# main.net
KiCad netlist of a schematic drawn in Altium Designer
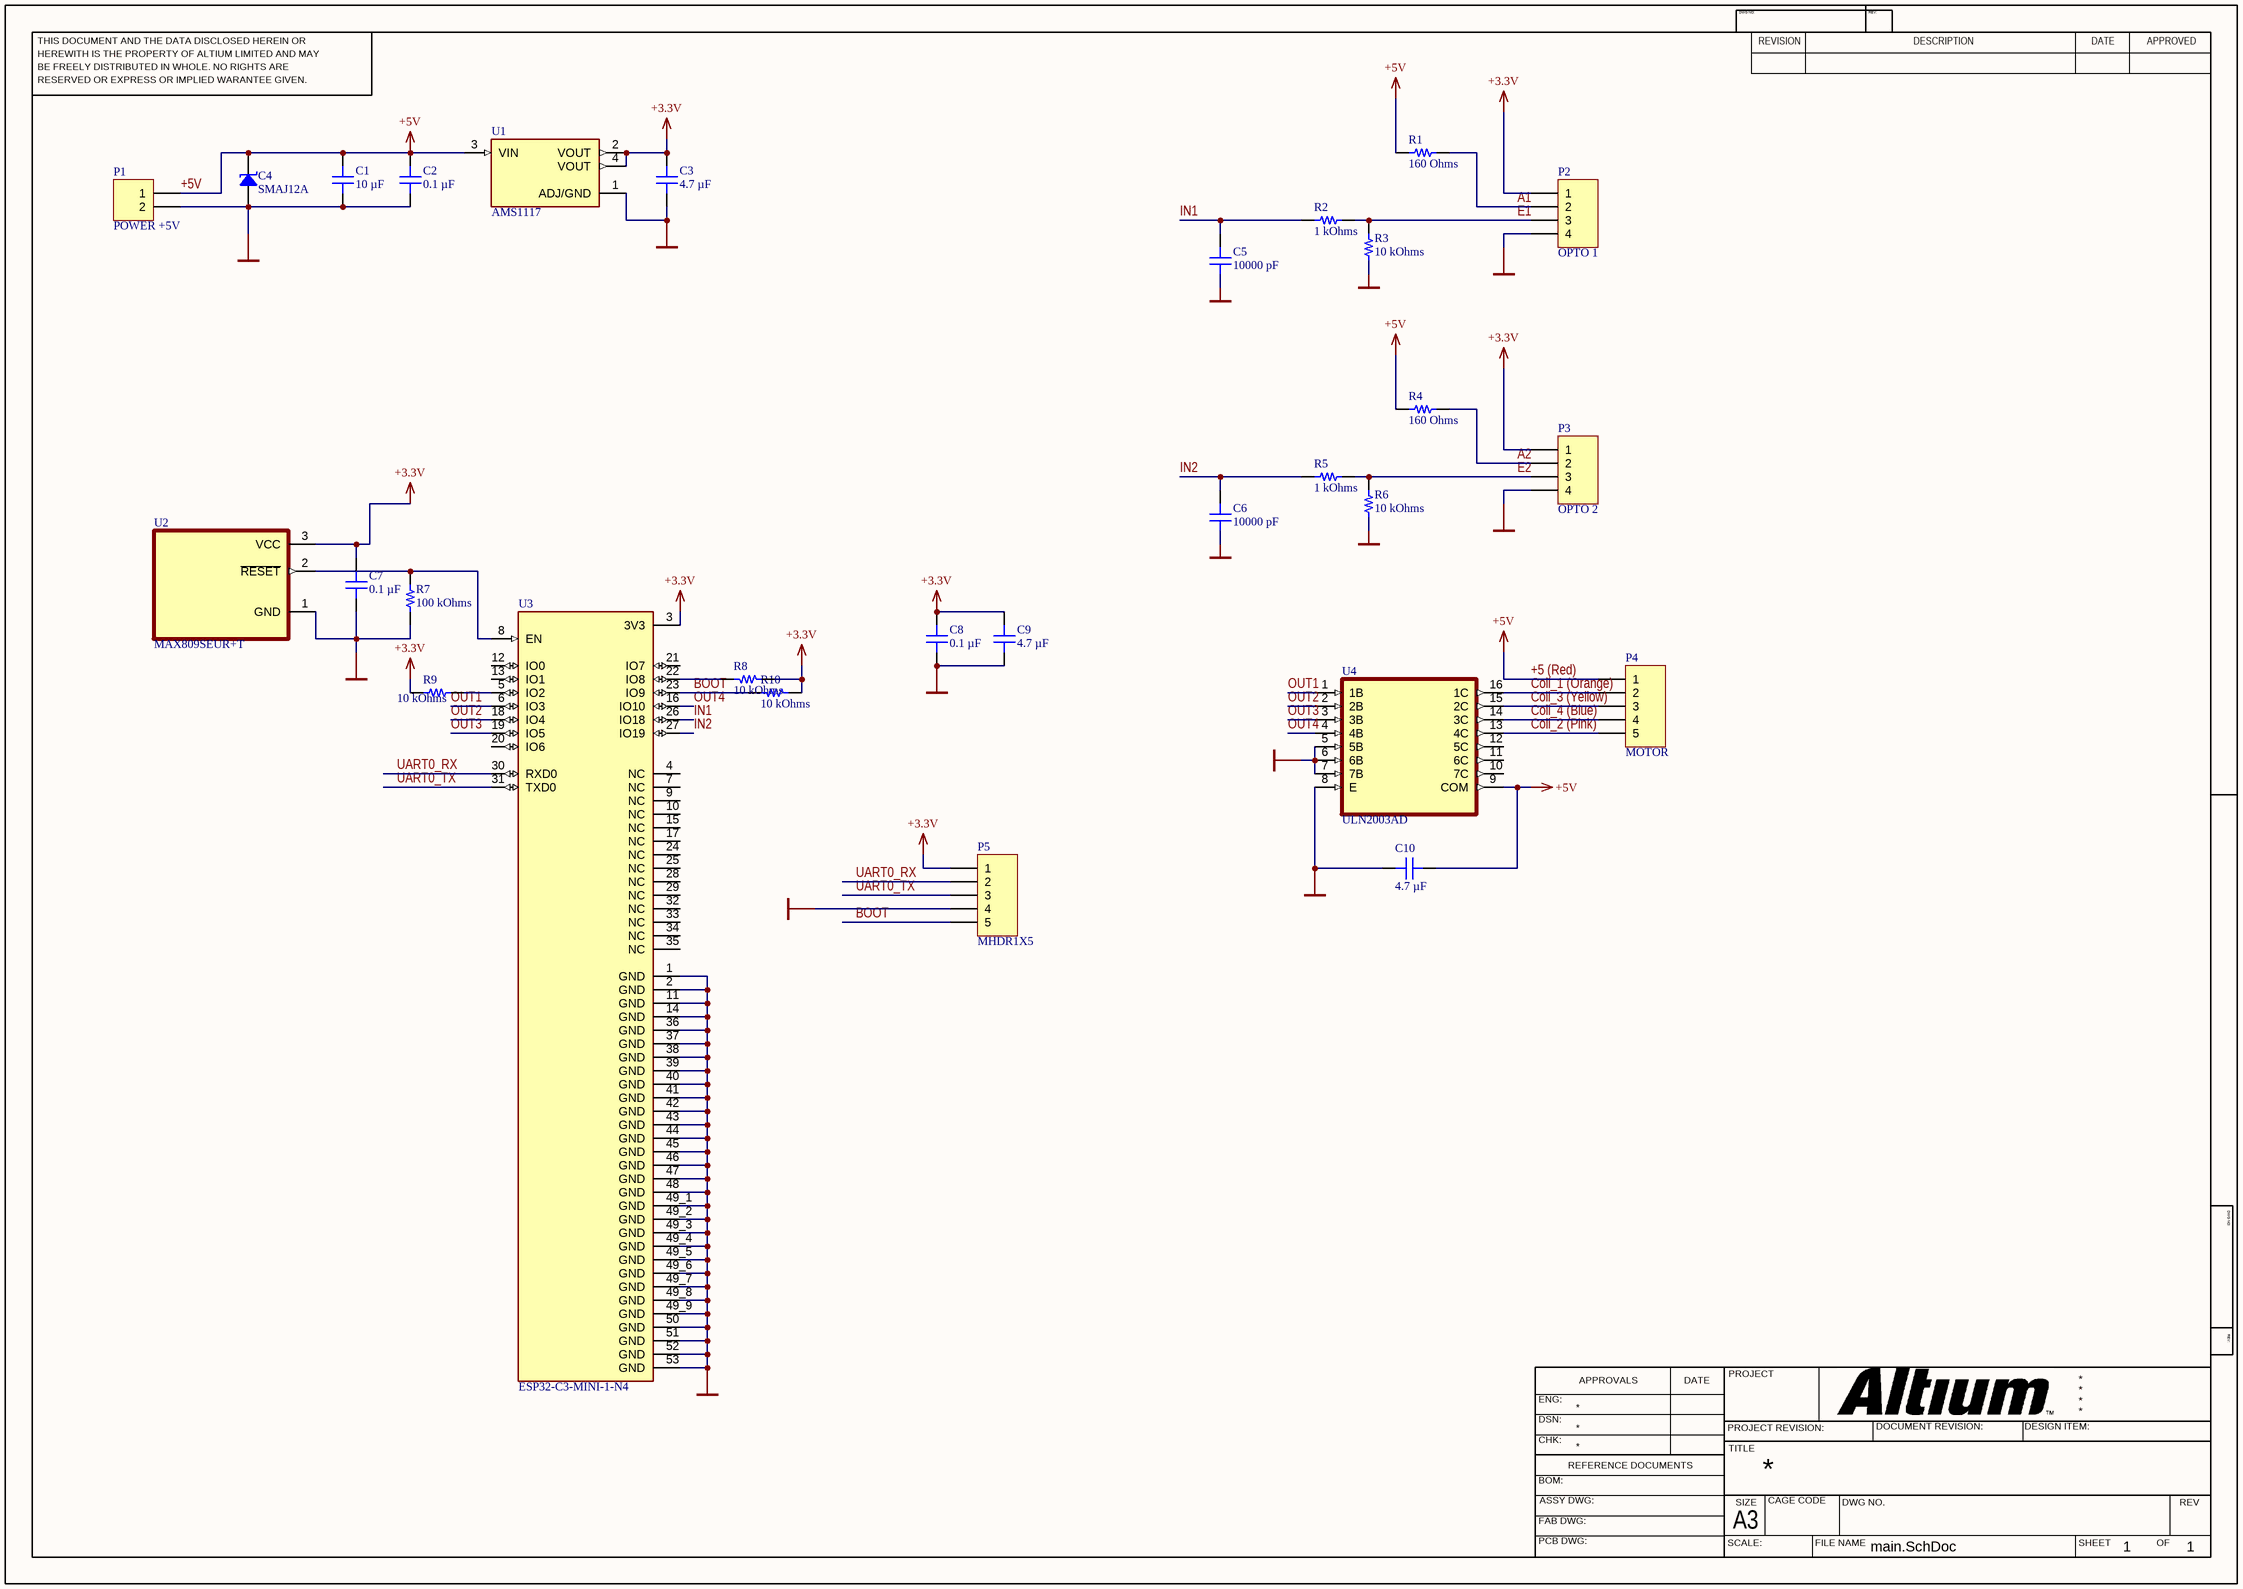
[diagram p0: main.SchDoc]

(export (version "E")
  (design (tool "Eeschema 10.0.6"))
  (components
    (comp (ref "C1")
      (value "10 µF")
      (footprint "CAP 0805_2012")
      (description "CAP CER 10UF 25V X5R 0805")
      (fields
        (field (name "PART NUMBER") "CC0805KKX5R8BB106")
        (field (name "CAPACITANCE") "10 µF")
        (field (name "MANUFACTURER") "Yageo")
      )
      (libsource (lib "Celestial Altium Library - altium_library") (part "Capacitor"))
    )
    (comp (ref "C2")
      (value "0.1 µF")
      (footprint "CAP 0603_1608")
      (description "CAP CER 0.1UF 50V X7R 0603")
      (fields
        (field (name "PART NUMBER") "CC0603KRX7R9BB104")
        (field (name "CAPACITANCE") "0.1 µF")
        (field (name "MANUFACTURER") "Yageo")
      )
      (libsource (lib "Celestial Altium Library - altium_library") (part "Capacitor"))
    )
    (comp (ref "C3")
      (value "~")
      (footprint "CAP 0603_1608")
      (description "CAP CER 4.7UF 6.3V X5R 0603")
      (fields (field (name "PART NUMBER") "C0603C475K9PAC7867") (field (name "CAPACITANCE") "4.7 µF"))
      (libsource (lib "Celestial Altium Library - altium_library") (part "Capacitor"))
    )
    (comp (ref "C4")
      (value "SMAJ12A")
      (footprint "DO214AC SMA")
      (description "TVS DIODE 12VWM 19.9VC DO214AC")
      (fields (field (name "MANUFACTURER") "Littelfuse Inc."))
      (libsource (lib "Celestial Altium Library - altium_library") (part "DIODE TVS UNI"))
    )
    (comp (ref "C5")
      (value "10000 pF")
      (footprint "CAP 0603_1608")
      (description "CAP CER 10000PF 50V X7R 0603")
      (fields
        (field (name "PART NUMBER") "CC0603KRX7R9BB103")
        (field (name "CAPACITANCE") "10000 pF")
        (field (name "MANUFACTURER") "Yageo")
      )
      (libsource (lib "Celestial Altium Library - altium_library") (part "Capacitor"))
    )
    (comp (ref "C6")
      (value "10000 pF")
      (footprint "CAP 0603_1608")
      (description "CAP CER 10000PF 50V X7R 0603")
      (fields
        (field (name "PART NUMBER") "CC0603KRX7R9BB103")
        (field (name "CAPACITANCE") "10000 pF")
        (field (name "MANUFACTURER") "Yageo")
      )
      (libsource (lib "Celestial Altium Library - altium_library") (part "Capacitor"))
    )
    (comp (ref "C7")
      (value "0.1 µF")
      (footprint "CAP 0603_1608")
      (description "CAP CER 0.1UF 50V X7R 0603")
      (fields
        (field (name "PART NUMBER") "CC0603KRX7R9BB104")
        (field (name "CAPACITANCE") "0.1 µF")
        (field (name "MANUFACTURER") "Yageo")
      )
      (libsource (lib "Celestial Altium Library - altium_library") (part "Capacitor"))
    )
    (comp (ref "C8")
      (value "0.1 µF")
      (footprint "CAP 0603_1608")
      (description "CAP CER 0.1UF 50V X7R 0603")
      (fields
        (field (name "PART NUMBER") "CC0603KRX7R9BB104")
        (field (name "CAPACITANCE") "0.1 µF")
        (field (name "MANUFACTURER") "Yageo")
      )
      (libsource (lib "Celestial Altium Library - altium_library") (part "Capacitor"))
    )
    (comp (ref "C9")
      (value "4.7 µF")
      (footprint "CAP 0603_1608")
      (description "CAP CER 4.7UF 6.3V X5R 0603")
      (fields
        (field (name "PART NUMBER") "C0603C475K9PAC7867")
        (field (name "CAPACITANCE") "4.7 µF")
        (field (name "MANUFACTURER") "KEMET")
      )
      (libsource (lib "Celestial Altium Library - altium_library") (part "Capacitor"))
    )
    (comp (ref "C10")
      (value "~")
      (footprint "CAP 0603_1608")
      (description "CAP CER 4.7UF 6.3V X5R 0603")
      (fields (field (name "PART NUMBER") "C0603C475K9PAC7867") (field (name "CAPACITANCE") "4.7 µF"))
      (libsource (lib "Celestial Altium Library - altium_library") (part "Capacitor"))
    )
    (comp (ref "P1")
      (value "POWER +5V")
      (footprint "HDR1X2H")
      (description "Header, 2-Pin, Right Angle")
      (fields (field (name "PUBLISHER") "Altium Limited"))
      (libsource (lib "Miscellaneous Connectors") (part "Header 2H"))
    )
    (comp (ref "P2")
      (value "OPTO 1")
      (footprint "HDR1X4H")
      (description "Header, 4-Pin, Right Angle")
      (fields (field (name "PUBLISHER") "Altium Limited"))
      (libsource (lib "Miscellaneous Connectors") (part "Header 4H"))
    )
    (comp (ref "P3")
      (value "OPTO 2")
      (footprint "HDR1X4H")
      (description "Header, 4-Pin, Right Angle")
      (fields (field (name "PUBLISHER") "Altium Limited"))
      (libsource (lib "Miscellaneous Connectors") (part "Header 4H"))
    )
    (comp (ref "P4")
      (value "MOTOR")
      (footprint "HDR1X5H")
      (description "Header, 5-Pin, Right Angle")
      (fields (field (name "PUBLISHER") "Altium Limited"))
      (libsource (lib "Miscellaneous Connectors") (part "Header 5H"))
    )
    (comp (ref "P5")
      (value "MHDR1X5")
      (footprint "MHDR1X5")
      (description "Header, 5-Pin")
      (fields (field (name "PUBLISHER") "Altium Limited"))
      (libsource (lib "Miscellaneous Connectors") (part "MHDR1X5"))
    )
    (comp (ref "R1")
      (value "160 Ohms")
      (footprint "YAGEO RES 0805_2012")
      (description "RES 160 OHM 5% 1/8W 0805")
      (fields (field (name "PART NUMBER") "RC0805JR-07160RL") (field (name "MANUFACTURER") "Yageo"))
      (libsource (lib "Celestial Altium Library - altium_library") (part "Resistor"))
    )
    (comp (ref "R2")
      (value "1 kOhms")
      (footprint "YAGEO RES 0603_1608")
      (description "RES 1K OHM 5% 1/10W 0603")
      (fields (field (name "PART NUMBER") "RC0603JR-071KL") (field (name "MANUFACTURER") "Yageo"))
      (libsource (lib "Celestial Altium Library - altium_library") (part "Resistor"))
    )
    (comp (ref "R3")
      (value "10 kOhms")
      (footprint "YAGEO RES 0603_1608")
      (description "RES 10K OHM 5% 1/10W 0603")
      (fields (field (name "PART NUMBER") "RC0603JR-0710KL") (field (name "MANUFACTURER") "Yageo"))
      (libsource (lib "Celestial Altium Library - altium_library") (part "Resistor"))
    )
    (comp (ref "R4")
      (value "160 Ohms")
      (footprint "YAGEO RES 0805_2012")
      (description "RES 160 OHM 5% 1/8W 0805")
      (fields (field (name "PART NUMBER") "RC0805JR-07160RL") (field (name "MANUFACTURER") "Yageo"))
      (libsource (lib "Celestial Altium Library - altium_library") (part "Resistor"))
    )
    (comp (ref "R5")
      (value "1 kOhms")
      (footprint "YAGEO RES 0603_1608")
      (description "RES 1K OHM 5% 1/10W 0603")
      (fields (field (name "PART NUMBER") "RC0603JR-071KL") (field (name "MANUFACTURER") "Yageo"))
      (libsource (lib "Celestial Altium Library - altium_library") (part "Resistor"))
    )
    (comp (ref "R6")
      (value "10 kOhms")
      (footprint "YAGEO RES 0603_1608")
      (description "RES 10K OHM 5% 1/10W 0603")
      (fields (field (name "PART NUMBER") "RC0603JR-0710KL") (field (name "MANUFACTURER") "Yageo"))
      (libsource (lib "Celestial Altium Library - altium_library") (part "Resistor"))
    )
    (comp (ref "R7")
      (value "100 kOhms")
      (footprint "YAGEO RES 0603_1608")
      (description "RES 100K OHM 5% 1/10W 0603")
      (fields (field (name "PART NUMBER") "RC0603JR-07100KL") (field (name "MANUFACTURER") "Yageo"))
      (libsource (lib "Celestial Altium Library - altium_library") (part "Resistor"))
    )
    (comp (ref "R8")
      (value "10 kOhms")
      (footprint "YAGEO RES 0603_1608")
      (description "RES 10K OHM 5% 1/10W 0603")
      (fields (field (name "PART NUMBER") "RC0603JR-0710KL") (field (name "MANUFACTURER") "Yageo"))
      (libsource (lib "Celestial Altium Library - altium_library") (part "Resistor"))
    )
    (comp (ref "R9")
      (value "10 kOhms")
      (footprint "YAGEO RES 0603_1608")
      (description "RES 10K OHM 5% 1/10W 0603")
      (fields (field (name "PART NUMBER") "RC0603JR-0710KL") (field (name "MANUFACTURER") "Yageo"))
      (libsource (lib "Celestial Altium Library - altium_library") (part "Resistor"))
    )
    (comp (ref "R10")
      (value "10 kOhms")
      (footprint "YAGEO RES 0603_1608")
      (description "RES 10K OHM 5% 1/10W 0603")
      (fields (field (name "PART NUMBER") "RC0603JR-0710KL") (field (name "MANUFACTURER") "Yageo"))
      (libsource (lib "Celestial Altium Library - altium_library") (part "Resistor"))
    )
    (comp (ref "U1")
      (value "AMS1117")
      (footprint "SOT229P700X180-4N")
      (description "1A LOW DROPOUT VOLTAGE REGULATOR SOT-223")
      (fields (field (name "MF") "Advanced Monolithic Systems"))
      (libsource (lib "AMS1117") (part "AMS1117"))
    )
    (comp (ref "U2")
      (value "MAX809SEUR+T")
      (footprint "SOT95P237X112-3N")
      (libsource (lib "MAX809SEUR_T") (part "MAX809SEUR+T"))
    )
    (comp (ref "U3")
      (value "ESP32-C3-MINI-1-N4")
      (footprint "XCVR_ESP32-C3-MINI-1-N4")
      (fields (field (name "MF") "Espressif Systems"))
      (libsource (lib "ESP32-C3-MINI-1-N4") (part "ESP32-C3-MINI-1-N4"))
    )
    (comp (ref "U4")
      (value "ULN2003AD")
      (footprint "SOIC127P600X175-16N")
      (description "50-V, 7-ch darlington transistor array, -20C to 70C")
      (fields (field (name "MF") "Texas Instruments"))
      (libsource (lib "ULN2003AD") (part "ULN2003AD"))
    )
  )
  (nets
    (net (code "1") (name "+3.3V") (class "Default")
      (node (ref "C3") (pin "2") (pinfunction "2_2") (pintype "passive"))
      (node (ref "C7") (pin "2") (pinfunction "2_2") (pintype "passive"))
      (node (ref "C8") (pin "2") (pinfunction "2_2") (pintype "passive"))
      (node (ref "C9") (pin "2") (pinfunction "2_2") (pintype "passive"))
      (node (ref "P2") (pin "1") (pinfunction "1_1") (pintype "passive"))
      (node (ref "P3") (pin "1") (pinfunction "1_1") (pintype "passive"))
      (node (ref "P5") (pin "1") (pinfunction "1_1") (pintype "passive"))
      (node (ref "R10") (pin "2") (pinfunction "2_2") (pintype "passive"))
      (node (ref "R8") (pin "2") (pinfunction "2_2") (pintype "passive"))
      (node (ref "R9") (pin "2") (pinfunction "2_2") (pintype "passive"))
      (node (ref "U1") (pin "2") (pinfunction "VOUT_2") (pintype "output"))
      (node (ref "U1") (pin "4") (pinfunction "VOUT_4") (pintype "output"))
      (node (ref "U2") (pin "3") (pinfunction "VCC_3") (pintype "power_in"))
      (node (ref "U3") (pin "3") (pinfunction "3V3_3") (pintype "power_in"))
    )
    (net (code "2") (name "+5V") (class "Default")
      (node (ref "C1") (pin "2") (pinfunction "2_2") (pintype "passive"))
      (node (ref "C10") (pin "1") (pinfunction "1_1") (pintype "passive"))
      (node (ref "C2") (pin "2") (pinfunction "2_2") (pintype "passive"))
      (node (ref "C4") (pin "2") (pinfunction "2_2") (pintype "passive"))
      (node (ref "P1") (pin "1") (pinfunction "1_1") (pintype "passive"))
      (node (ref "P4") (pin "1") (pinfunction "1_1") (pintype "passive"))
      (node (ref "R1") (pin "2") (pinfunction "2_2") (pintype "passive"))
      (node (ref "R4") (pin "2") (pinfunction "2_2") (pintype "passive"))
      (node (ref "U1") (pin "3") (pinfunction "VIN_3") (pintype "input"))
      (node (ref "U4") (pin "9") (pinfunction "COM_9") (pintype "output"))
    )
    (net (code "3") (name "/A1") (class "Default")
      (node (ref "P2") (pin "2") (pinfunction "2_2") (pintype "passive"))
      (node (ref "R1") (pin "1") (pinfunction "1_1") (pintype "passive"))
    )
    (net (code "4") (name "/A2") (class "Default")
      (node (ref "P3") (pin "2") (pinfunction "2_2") (pintype "passive"))
      (node (ref "R4") (pin "1") (pinfunction "1_1") (pintype "passive"))
    )
    (net (code "5") (name "/BOOT") (class "Default")
      (node (ref "P5") (pin "5") (pinfunction "5_5") (pintype "passive"))
      (node (ref "R10") (pin "1") (pinfunction "1_1") (pintype "passive"))
      (node (ref "U3") (pin "23") (pinfunction "IO9_23") (pintype "bidirectional"))
    )
    (net (code "6") (name "/Coil_1 (Orange)") (class "Default")
      (node (ref "P4") (pin "2") (pinfunction "2_2") (pintype "passive"))
      (node (ref "U4") (pin "16") (pinfunction "1C_16") (pintype "output"))
    )
    (net (code "7") (name "/Coil_2 (Pink)") (class "Default")
      (node (ref "P4") (pin "5") (pinfunction "5_5") (pintype "passive"))
      (node (ref "U4") (pin "13") (pinfunction "4C_13") (pintype "output"))
    )
    (net (code "8") (name "/Coil_3 (Yellow)") (class "Default")
      (node (ref "P4") (pin "3") (pinfunction "3_3") (pintype "passive"))
      (node (ref "U4") (pin "15") (pinfunction "2C_15") (pintype "output"))
    )
    (net (code "9") (name "/Coil_4 (Blue)") (class "Default")
      (node (ref "P4") (pin "4") (pinfunction "4_4") (pintype "passive"))
      (node (ref "U4") (pin "14") (pinfunction "3C_14") (pintype "output"))
    )
    (net (code "10") (name "/E1") (class "Default")
      (node (ref "P2") (pin "3") (pinfunction "3_3") (pintype "passive"))
      (node (ref "R2") (pin "1") (pinfunction "1_1") (pintype "passive"))
      (node (ref "R3") (pin "2") (pinfunction "2_2") (pintype "passive"))
    )
    (net (code "11") (name "/E2") (class "Default")
      (node (ref "P3") (pin "3") (pinfunction "3_3") (pintype "passive"))
      (node (ref "R5") (pin "1") (pinfunction "1_1") (pintype "passive"))
      (node (ref "R6") (pin "2") (pinfunction "2_2") (pintype "passive"))
    )
    (net (code "12") (name "/IN1") (class "Default")
      (node (ref "C5") (pin "2") (pinfunction "2_2") (pintype "passive"))
      (node (ref "R2") (pin "2") (pinfunction "2_2") (pintype "passive"))
      (node (ref "U3") (pin "26") (pinfunction "IO18_26") (pintype "bidirectional"))
    )
    (net (code "13") (name "/IN2") (class "Default")
      (node (ref "C6") (pin "2") (pinfunction "2_2") (pintype "passive"))
      (node (ref "R5") (pin "2") (pinfunction "2_2") (pintype "passive"))
      (node (ref "U3") (pin "27") (pinfunction "IO19_27") (pintype "bidirectional"))
    )
    (net (code "14") (name "/OUT1") (class "Default")
      (node (ref "U3") (pin "6") (pinfunction "IO3_6") (pintype "bidirectional"))
      (node (ref "U4") (pin "1") (pinfunction "1B_1") (pintype "input"))
    )
    (net (code "15") (name "/OUT2") (class "Default")
      (node (ref "U3") (pin "18") (pinfunction "IO4_18") (pintype "bidirectional"))
      (node (ref "U4") (pin "2") (pinfunction "2B_2") (pintype "input"))
    )
    (net (code "16") (name "/OUT3") (class "Default")
      (node (ref "U3") (pin "19") (pinfunction "IO5_19") (pintype "bidirectional"))
      (node (ref "U4") (pin "3") (pinfunction "3B_3") (pintype "input"))
    )
    (net (code "17") (name "/OUT4") (class "Default")
      (node (ref "U3") (pin "16") (pinfunction "IO10_16") (pintype "bidirectional"))
      (node (ref "U4") (pin "4") (pinfunction "4B_4") (pintype "input"))
    )
    (net (code "18") (name "/UART0_RX") (class "Default")
      (node (ref "P5") (pin "2") (pinfunction "2_2") (pintype "passive"))
      (node (ref "U3") (pin "30") (pinfunction "RXD0_30") (pintype "bidirectional"))
    )
    (net (code "19") (name "/UART0_TX") (class "Default")
      (node (ref "P5") (pin "3") (pinfunction "3_3") (pintype "passive"))
      (node (ref "U3") (pin "31") (pinfunction "TXD0_31") (pintype "bidirectional"))
    )
    (net (code "20") (name "GND") (class "Default")
      (node (ref "C1") (pin "1") (pinfunction "1_1") (pintype "passive"))
      (node (ref "C10") (pin "2") (pinfunction "2_2") (pintype "passive"))
      (node (ref "C2") (pin "1") (pinfunction "1_1") (pintype "passive"))
      (node (ref "C3") (pin "1") (pinfunction "1_1") (pintype "passive"))
      (node (ref "C4") (pin "1") (pinfunction "1_1") (pintype "passive"))
      (node (ref "C5") (pin "1") (pinfunction "1_1") (pintype "passive"))
      (node (ref "C6") (pin "1") (pinfunction "1_1") (pintype "passive"))
      (node (ref "C7") (pin "1") (pinfunction "1_1") (pintype "passive"))
      (node (ref "C8") (pin "1") (pinfunction "1_1") (pintype "passive"))
      (node (ref "C9") (pin "1") (pinfunction "1_1") (pintype "passive"))
      (node (ref "P1") (pin "2") (pinfunction "2_2") (pintype "passive"))
      (node (ref "P2") (pin "4") (pinfunction "4_4") (pintype "passive"))
      (node (ref "P3") (pin "4") (pinfunction "4_4") (pintype "passive"))
      (node (ref "P5") (pin "4") (pinfunction "4_4") (pintype "passive"))
      (node (ref "R3") (pin "1") (pinfunction "1_1") (pintype "passive"))
      (node (ref "R6") (pin "1") (pinfunction "1_1") (pintype "passive"))
      (node (ref "R7") (pin "1") (pinfunction "1_1") (pintype "passive"))
      (node (ref "U1") (pin "1") (pinfunction "ADJ/GND_1") (pintype "power_in"))
      (node (ref "U2") (pin "1") (pinfunction "GND_1") (pintype "power_in"))
      (node (ref "U3") (pin "1") (pinfunction "GND_1") (pintype "power_in"))
      (node (ref "U3") (pin "11") (pinfunction "GND_11") (pintype "power_in"))
      (node (ref "U3") (pin "14") (pinfunction "GND_14") (pintype "power_in"))
      (node (ref "U3") (pin "2") (pinfunction "GND_2") (pintype "power_in"))
      (node (ref "U3") (pin "36") (pinfunction "GND_36") (pintype "power_in"))
      (node (ref "U3") (pin "37") (pinfunction "GND_37") (pintype "power_in"))
      (node (ref "U3") (pin "38") (pinfunction "GND_38") (pintype "power_in"))
      (node (ref "U3") (pin "39") (pinfunction "GND_39") (pintype "power_in"))
      (node (ref "U3") (pin "40") (pinfunction "GND_40") (pintype "power_in"))
      (node (ref "U3") (pin "41") (pinfunction "GND_41") (pintype "power_in"))
      (node (ref "U3") (pin "42") (pinfunction "GND_42") (pintype "power_in"))
      (node (ref "U3") (pin "43") (pinfunction "GND_43") (pintype "power_in"))
      (node (ref "U3") (pin "44") (pinfunction "GND_44") (pintype "power_in"))
      (node (ref "U3") (pin "45") (pinfunction "GND_45") (pintype "power_in"))
      (node (ref "U3") (pin "46") (pinfunction "GND_46") (pintype "power_in"))
      (node (ref "U3") (pin "47") (pinfunction "GND_47") (pintype "power_in"))
      (node (ref "U3") (pin "48") (pinfunction "GND_48") (pintype "power_in"))
      (node (ref "U3") (pin "49_1") (pinfunction "GND_49_1") (pintype "power_in"))
      (node (ref "U3") (pin "49_2") (pinfunction "GND_49_2") (pintype "power_in"))
      (node (ref "U3") (pin "49_3") (pinfunction "GND_49_3") (pintype "power_in"))
      (node (ref "U3") (pin "49_4") (pinfunction "GND_49_4") (pintype "power_in"))
      (node (ref "U3") (pin "49_5") (pinfunction "GND_49_5") (pintype "power_in"))
      (node (ref "U3") (pin "49_6") (pinfunction "GND_49_6") (pintype "power_in"))
      (node (ref "U3") (pin "49_7") (pinfunction "GND_49_7") (pintype "power_in"))
      (node (ref "U3") (pin "49_8") (pinfunction "GND_49_8") (pintype "power_in"))
      (node (ref "U3") (pin "49_9") (pinfunction "GND_49_9") (pintype "power_in"))
      (node (ref "U3") (pin "50") (pinfunction "GND_50") (pintype "power_in"))
      (node (ref "U3") (pin "51") (pinfunction "GND_51") (pintype "power_in"))
      (node (ref "U3") (pin "52") (pinfunction "GND_52") (pintype "power_in"))
      (node (ref "U3") (pin "53") (pinfunction "GND_53") (pintype "power_in"))
      (node (ref "U4") (pin "5") (pinfunction "5B_5") (pintype "input"))
      (node (ref "U4") (pin "6") (pinfunction "6B_6") (pintype "input"))
      (node (ref "U4") (pin "7") (pinfunction "7B_7") (pintype "input"))
      (node (ref "U4") (pin "8") (pinfunction "E_8") (pintype "input"))
    )
    (net (code "21") (name "Net-(U2-~{RESET})") (class "Default")
      (node (ref "R7") (pin "2") (pinfunction "2_2") (pintype "passive"))
      (node (ref "U2") (pin "2") (pinfunction "~{RESET}_2") (pintype "output"))
      (node (ref "U3") (pin "8") (pinfunction "EN_8") (pintype "input"))
    )
    (net (code "22") (name "Net-(U3-IO2)") (class "Default")
      (node (ref "R9") (pin "1") (pinfunction "1_1") (pintype "passive"))
      (node (ref "U3") (pin "5") (pinfunction "IO2_5") (pintype "bidirectional"))
    )
    (net (code "23") (name "Net-(U3-IO8)") (class "Default")
      (node (ref "R8") (pin "1") (pinfunction "1_1") (pintype "passive"))
      (node (ref "U3") (pin "22") (pinfunction "IO8_22") (pintype "bidirectional"))
    )
    (net (code "24") (name "unconnected-(U3-IO0-Pad12)") (class "Default")
      (node (ref "U3") (pin "12") (pinfunction "IO0_12") (pintype "bidirectional"))
    )
    (net (code "25") (name "unconnected-(U3-IO1-Pad13)") (class "Default")
      (node (ref "U3") (pin "13") (pinfunction "IO1_13") (pintype "bidirectional"))
    )
    (net (code "26") (name "unconnected-(U3-IO6-Pad20)") (class "Default")
      (node (ref "U3") (pin "20") (pinfunction "IO6_20") (pintype "bidirectional"))
    )
    (net (code "27") (name "unconnected-(U3-IO7-Pad21)") (class "Default")
      (node (ref "U3") (pin "21") (pinfunction "IO7_21") (pintype "bidirectional"))
    )
    (net (code "28") (name "unconnected-(U3-NC-Pad4)") (class "Default")
      (node (ref "U3") (pin "4") (pinfunction "NC_4") (pintype "passive"))
    )
    (net (code "29") (name "unconnected-(U3-NC-Pad7)") (class "Default")
      (node (ref "U3") (pin "7") (pinfunction "NC_7") (pintype "passive"))
    )
    (net (code "30") (name "unconnected-(U3-NC-Pad9)") (class "Default")
      (node (ref "U3") (pin "9") (pinfunction "NC_9") (pintype "passive"))
    )
    (net (code "31") (name "unconnected-(U3-NC-Pad10)") (class "Default")
      (node (ref "U3") (pin "10") (pinfunction "NC_10") (pintype "passive"))
    )
    (net (code "32") (name "unconnected-(U3-NC-Pad15)") (class "Default")
      (node (ref "U3") (pin "15") (pinfunction "NC_15") (pintype "passive"))
    )
    (net (code "33") (name "unconnected-(U3-NC-Pad17)") (class "Default")
      (node (ref "U3") (pin "17") (pinfunction "NC_17") (pintype "passive"))
    )
    (net (code "34") (name "unconnected-(U3-NC-Pad24)") (class "Default")
      (node (ref "U3") (pin "24") (pinfunction "NC_24") (pintype "passive"))
    )
    (net (code "35") (name "unconnected-(U3-NC-Pad25)") (class "Default")
      (node (ref "U3") (pin "25") (pinfunction "NC_25") (pintype "passive"))
    )
    (net (code "36") (name "unconnected-(U3-NC-Pad28)") (class "Default")
      (node (ref "U3") (pin "28") (pinfunction "NC_28") (pintype "passive"))
    )
    (net (code "37") (name "unconnected-(U3-NC-Pad29)") (class "Default")
      (node (ref "U3") (pin "29") (pinfunction "NC_29") (pintype "passive"))
    )
    (net (code "38") (name "unconnected-(U3-NC-Pad32)") (class "Default")
      (node (ref "U3") (pin "32") (pinfunction "NC_32") (pintype "passive"))
    )
    (net (code "39") (name "unconnected-(U3-NC-Pad33)") (class "Default")
      (node (ref "U3") (pin "33") (pinfunction "NC_33") (pintype "passive"))
    )
    (net (code "40") (name "unconnected-(U3-NC-Pad34)") (class "Default")
      (node (ref "U3") (pin "34") (pinfunction "NC_34") (pintype "passive"))
    )
    (net (code "41") (name "unconnected-(U3-NC-Pad35)") (class "Default")
      (node (ref "U3") (pin "35") (pinfunction "NC_35") (pintype "passive"))
    )
    (net (code "42") (name "unconnected-(U4-5C-Pad12)") (class "Default")
      (node (ref "U4") (pin "12") (pinfunction "5C_12") (pintype "output"))
    )
    (net (code "43") (name "unconnected-(U4-6C-Pad11)") (class "Default")
      (node (ref "U4") (pin "11") (pinfunction "6C_11") (pintype "output"))
    )
    (net (code "44") (name "unconnected-(U4-7C-Pad10)") (class "Default")
      (node (ref "U4") (pin "10") (pinfunction "7C_10") (pintype "output"))
    )
  )
)
